# exp1.net
KiCad netlist of a schematic drawn in EAGLE
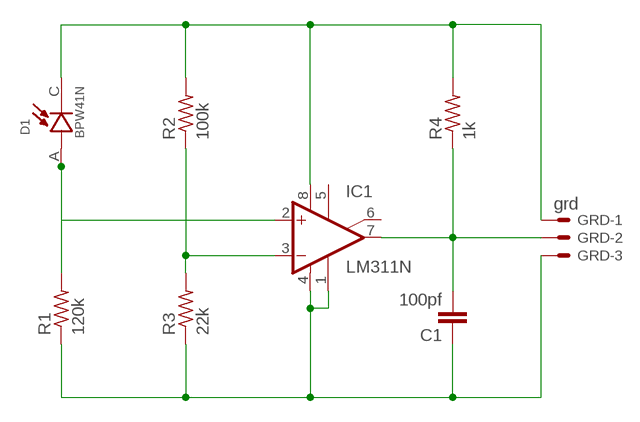
[diagram p0: schematic, sheet 1]

(export (version "E")
  (design (tool "Eeschema 10.0.6"))
  (components
    (comp (ref "C1")
      (value "100pf")
      (footprint "eagle-import:C2.5-3")
      (libsource (lib "eagle-import") (part "C2,5-3"))
    )
    (comp (ref "D1")
      (value "BPW41N")
      (footprint "eagle-import:DIO_BPW41N")
      (fields (field (name "MF") "Vishay Semiconductor Opto Division"))
      (libsource (lib "eagle-import") (part "BPW41N"))
    )
    (comp (ref "GRD")
      (value "grd")
      (footprint "eagle-import:22-23-2031")
      (fields (field (name "MF") "MOLEX") (field (name "MPN") "22-23-2031"))
      (libsource (lib "eagle-import") (part "22-23-2031"))
    )
    (comp (ref "IC1")
      (value "LM311N")
      (footprint "eagle-import:DIL08")
      (libsource (lib "eagle-import") (part "LM311N"))
    )
    (comp (ref "R1")
      (value "120k")
      (footprint "eagle-import:0207_10")
      (libsource (lib "eagle-import") (part "R-US_0207/10"))
    )
    (comp (ref "R2")
      (value "100k")
      (footprint "eagle-import:0207_10")
      (libsource (lib "eagle-import") (part "R-US_0207/10"))
    )
    (comp (ref "R3")
      (value "22k")
      (footprint "eagle-import:0207_10")
      (libsource (lib "eagle-import") (part "R-US_0207/10"))
    )
    (comp (ref "R4")
      (value "1k")
      (footprint "eagle-import:0207_10")
      (libsource (lib "eagle-import") (part "R-US_0207/10"))
    )
  )
  (nets
    (net (code "1") (name "Net-(GRDA-S)") (class "Default")
      (node (ref "D1") (pin "C") (pinfunction "C_C") (pintype "passive"))
      (node (ref "GRD") (pin "1") (pinfunction "S_1") (pintype "passive"))
      (node (ref "IC1") (pin "8") (pinfunction "V+_8") (pintype "power_in"))
      (node (ref "R2") (pin "2") (pinfunction "2_2") (pintype "passive"))
      (node (ref "R4") (pin "2") (pinfunction "2_2") (pintype "passive"))
    )
    (net (code "2") (name "Net-(GRDB-S)") (class "Default")
      (node (ref "C1") (pin "2") (pinfunction "2_2") (pintype "passive"))
      (node (ref "GRD") (pin "2") (pinfunction "S_2") (pintype "passive"))
      (node (ref "IC1") (pin "7") (pinfunction "OUT_7") (pintype "output"))
      (node (ref "R4") (pin "1") (pinfunction "1_1") (pintype "passive"))
    )
    (net (code "3") (name "Net-(GRDC-S)") (class "Default")
      (node (ref "C1") (pin "1") (pinfunction "1_1") (pintype "passive"))
      (node (ref "GRD") (pin "3") (pinfunction "S_3") (pintype "passive"))
      (node (ref "IC1") (pin "1") (pinfunction "GND_1") (pintype "passive"))
      (node (ref "IC1") (pin "4") (pinfunction "V-_4") (pintype "power_in"))
      (node (ref "R1") (pin "1") (pinfunction "1_1") (pintype "passive"))
      (node (ref "R3") (pin "1") (pinfunction "1_1") (pintype "passive"))
    )
    (net (code "4") (name "Net-(IC1-+IN)") (class "Default")
      (node (ref "D1") (pin "A") (pinfunction "A_A") (pintype "passive"))
      (node (ref "IC1") (pin "2") (pinfunction "+IN_2") (pintype "input"))
      (node (ref "R1") (pin "2") (pinfunction "2_2") (pintype "passive"))
    )
    (net (code "5") (name "Net-(IC1--IN)") (class "Default")
      (node (ref "IC1") (pin "3") (pinfunction "-IN_3") (pintype "input"))
      (node (ref "R2") (pin "1") (pinfunction "1_1") (pintype "passive"))
      (node (ref "R3") (pin "2") (pinfunction "2_2") (pintype "passive"))
    )
    (net (code "6") (name "unconnected-(IC1-ON-Pad5)") (class "Default")
      (node (ref "IC1") (pin "5") (pinfunction "ON_5") (pintype "passive"))
    )
    (net (code "7") (name "unconnected-(IC1-ON{slash}STR-Pad6)") (class "Default")
      (node (ref "IC1") (pin "6") (pinfunction "ON/STR_6") (pintype "passive"))
    )
  )
)
